# PATA_Breakout_2.net
KiCad netlist of a schematic drawn in EAGLE
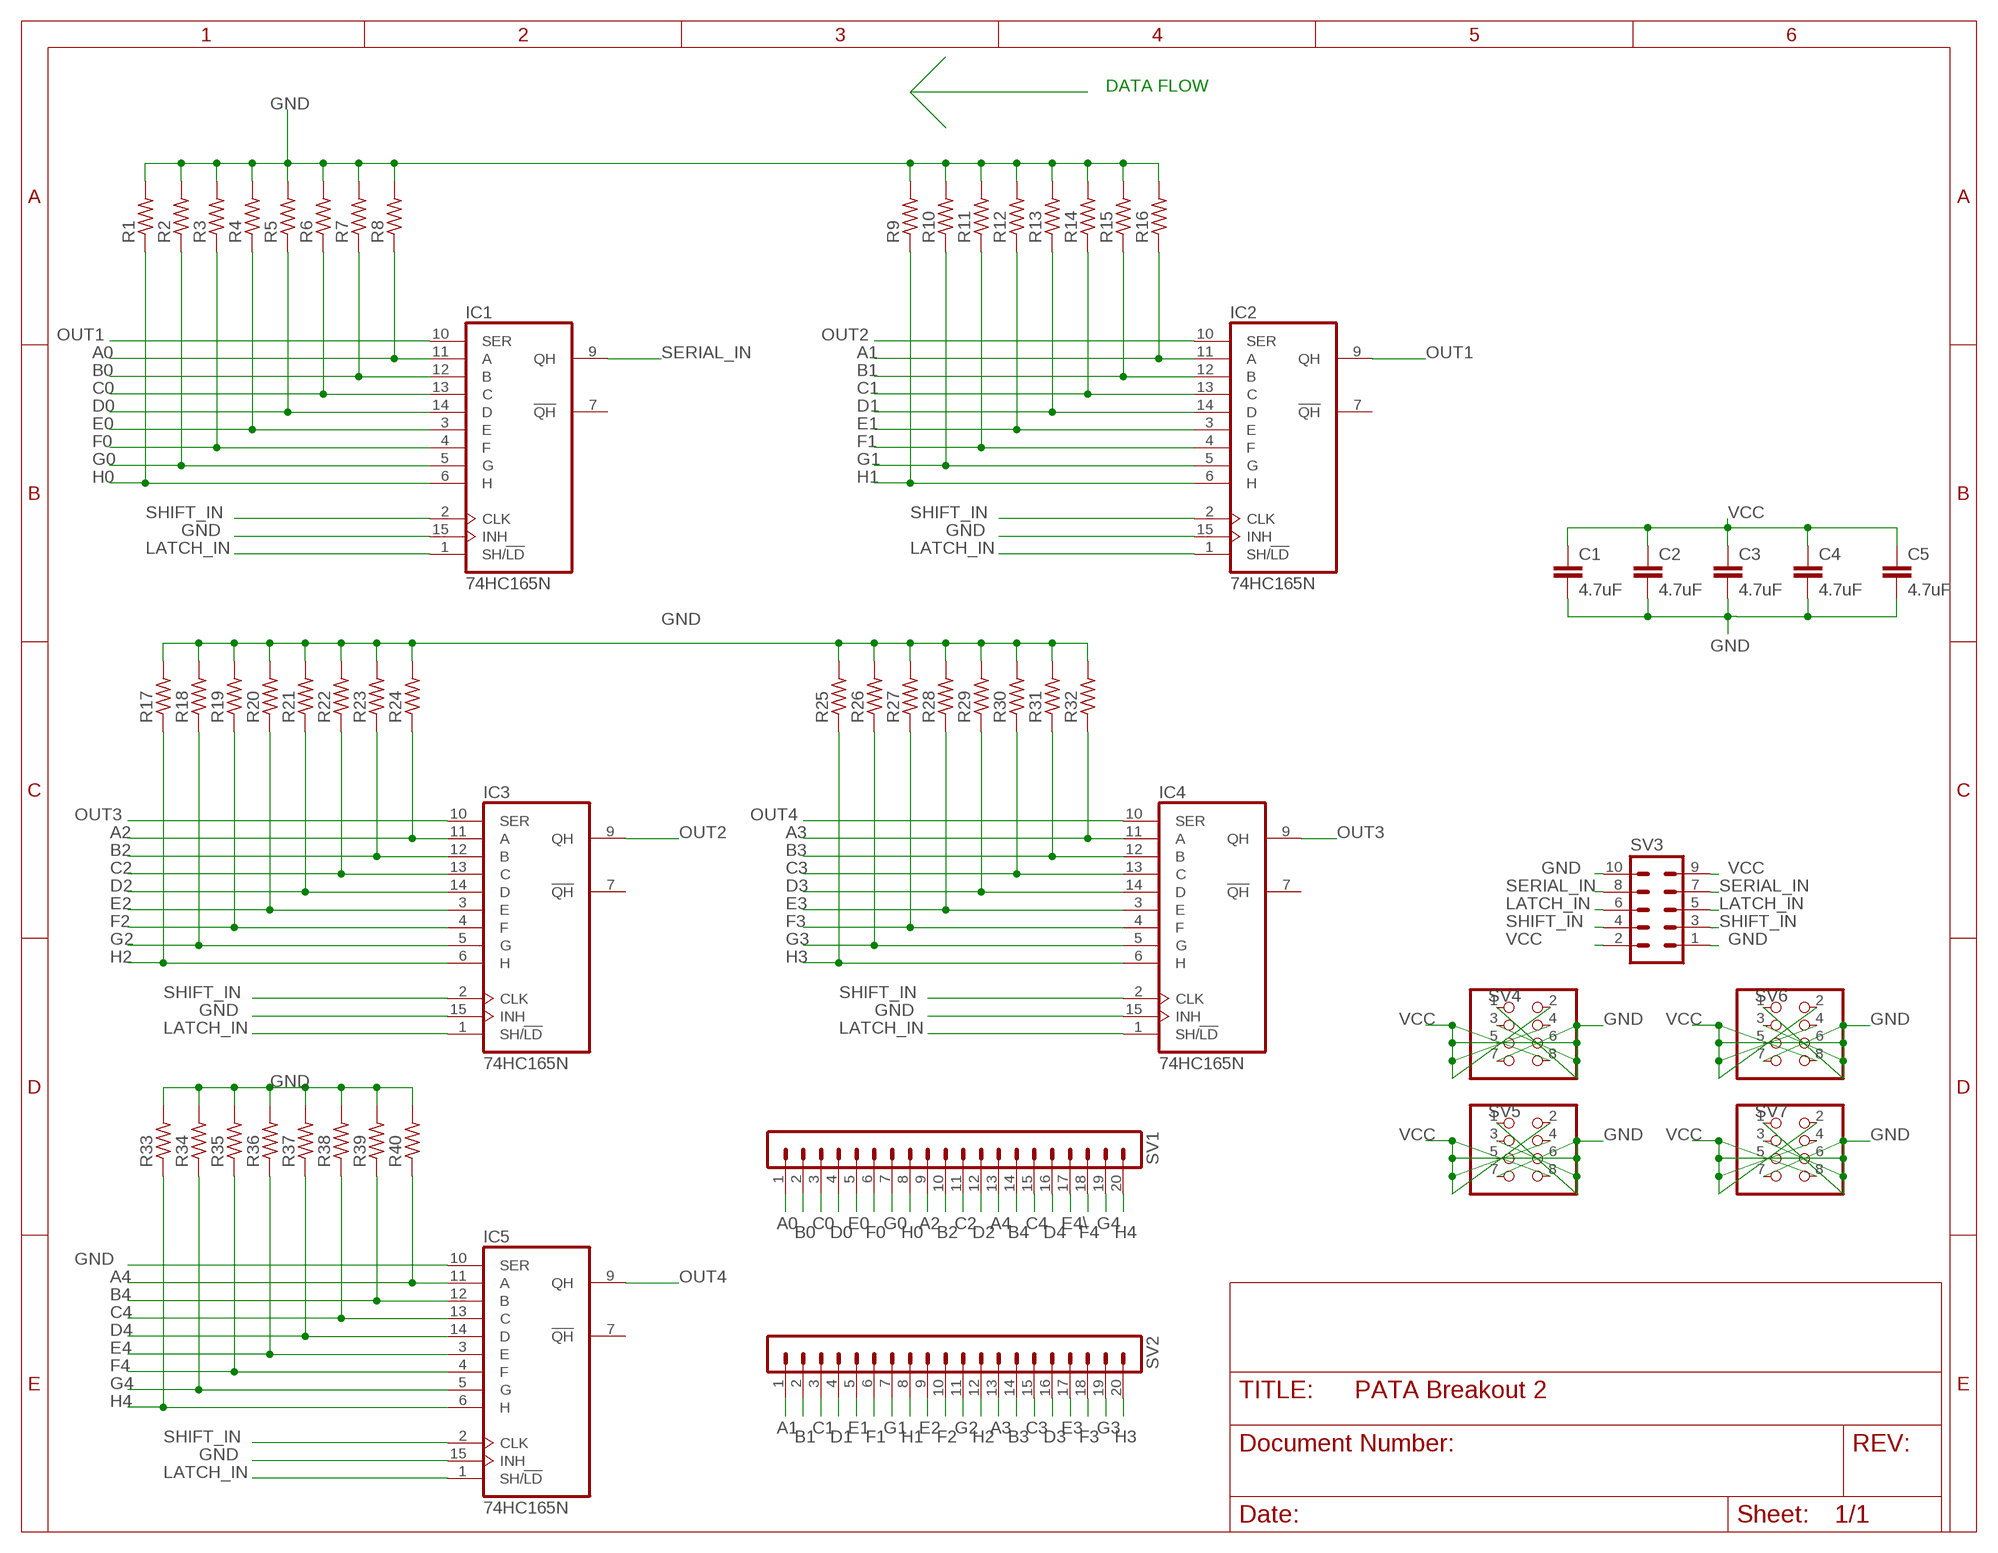
[diagram p0: schematic, sheet 1]

(export (version "E")
  (design (tool "Eeschema 10.0.6"))
  (components
    (comp (ref "C1")
      (value "4.7uF")
      (footprint "eagle-import:C050-024X044")
      (libsource (lib "eagle-import") (part "C-EU050-024X044"))
    )
    (comp (ref "C2")
      (value "4.7uF")
      (footprint "eagle-import:C050-024X044")
      (libsource (lib "eagle-import") (part "C-EU050-024X044"))
    )
    (comp (ref "C3")
      (value "4.7uF")
      (footprint "eagle-import:C050-024X044")
      (libsource (lib "eagle-import") (part "C-EU050-024X044"))
    )
    (comp (ref "C4")
      (value "4.7uF")
      (footprint "eagle-import:C050-024X044")
      (libsource (lib "eagle-import") (part "C-EU050-024X044"))
    )
    (comp (ref "C5")
      (value "4.7uF")
      (footprint "eagle-import:C050-024X044")
      (libsource (lib "eagle-import") (part "C-EU050-024X044"))
    )
    (comp (ref "IC1")
      (value "74HC165N")
      (footprint "eagle-import:DIL16")
      (libsource (lib "eagle-import") (part "74165NHC"))
    )
    (comp (ref "IC2")
      (value "74HC165N")
      (footprint "eagle-import:DIL16")
      (libsource (lib "eagle-import") (part "74165NHC"))
    )
    (comp (ref "IC3")
      (value "74HC165N")
      (footprint "eagle-import:DIL16")
      (libsource (lib "eagle-import") (part "74165NHC"))
    )
    (comp (ref "IC4")
      (value "74HC165N")
      (footprint "eagle-import:DIL16")
      (libsource (lib "eagle-import") (part "74165NHC"))
    )
    (comp (ref "IC5")
      (value "74HC165N")
      (footprint "eagle-import:DIL16")
      (libsource (lib "eagle-import") (part "74165NHC"))
    )
    (comp (ref "R1")
      (value "R-US_0204/5")
      (footprint "eagle-import:0204_5")
      (libsource (lib "eagle-import") (part "R-US_0204/5"))
    )
    (comp (ref "R2")
      (value "R-US_0204/5")
      (footprint "eagle-import:0204_5")
      (libsource (lib "eagle-import") (part "R-US_0204/5"))
    )
    (comp (ref "R3")
      (value "R-US_0204/5")
      (footprint "eagle-import:0204_5")
      (libsource (lib "eagle-import") (part "R-US_0204/5"))
    )
    (comp (ref "R4")
      (value "R-US_0204/5")
      (footprint "eagle-import:0204_5")
      (libsource (lib "eagle-import") (part "R-US_0204/5"))
    )
    (comp (ref "R5")
      (value "R-US_0204/5")
      (footprint "eagle-import:0204_5")
      (libsource (lib "eagle-import") (part "R-US_0204/5"))
    )
    (comp (ref "R6")
      (value "R-US_0204/5")
      (footprint "eagle-import:0204_5")
      (libsource (lib "eagle-import") (part "R-US_0204/5"))
    )
    (comp (ref "R7")
      (value "R-US_0204/5")
      (footprint "eagle-import:0204_5")
      (libsource (lib "eagle-import") (part "R-US_0204/5"))
    )
    (comp (ref "R8")
      (value "R-US_0204/5")
      (footprint "eagle-import:0204_5")
      (libsource (lib "eagle-import") (part "R-US_0204/5"))
    )
    (comp (ref "R9")
      (value "R-US_0204/5")
      (footprint "eagle-import:0204_5")
      (libsource (lib "eagle-import") (part "R-US_0204/5"))
    )
    (comp (ref "R10")
      (value "R-US_0204/5")
      (footprint "eagle-import:0204_5")
      (libsource (lib "eagle-import") (part "R-US_0204/5"))
    )
    (comp (ref "R11")
      (value "R-US_0204/5")
      (footprint "eagle-import:0204_5")
      (libsource (lib "eagle-import") (part "R-US_0204/5"))
    )
    (comp (ref "R12")
      (value "R-US_0204/5")
      (footprint "eagle-import:0204_5")
      (libsource (lib "eagle-import") (part "R-US_0204/5"))
    )
    (comp (ref "R13")
      (value "R-US_0204/5")
      (footprint "eagle-import:0204_5")
      (libsource (lib "eagle-import") (part "R-US_0204/5"))
    )
    (comp (ref "R14")
      (value "R-US_0204/5")
      (footprint "eagle-import:0204_5")
      (libsource (lib "eagle-import") (part "R-US_0204/5"))
    )
    (comp (ref "R15")
      (value "R-US_0204/5")
      (footprint "eagle-import:0204_5")
      (libsource (lib "eagle-import") (part "R-US_0204/5"))
    )
    (comp (ref "R16")
      (value "R-US_0204/5")
      (footprint "eagle-import:0204_5")
      (libsource (lib "eagle-import") (part "R-US_0204/5"))
    )
    (comp (ref "R17")
      (value "R-US_0204/5")
      (footprint "eagle-import:0204_5")
      (libsource (lib "eagle-import") (part "R-US_0204/5"))
    )
    (comp (ref "R18")
      (value "R-US_0204/5")
      (footprint "eagle-import:0204_5")
      (libsource (lib "eagle-import") (part "R-US_0204/5"))
    )
    (comp (ref "R19")
      (value "R-US_0204/5")
      (footprint "eagle-import:0204_5")
      (libsource (lib "eagle-import") (part "R-US_0204/5"))
    )
    (comp (ref "R20")
      (value "R-US_0204/5")
      (footprint "eagle-import:0204_5")
      (libsource (lib "eagle-import") (part "R-US_0204/5"))
    )
    (comp (ref "R21")
      (value "R-US_0204/5")
      (footprint "eagle-import:0204_5")
      (libsource (lib "eagle-import") (part "R-US_0204/5"))
    )
    (comp (ref "R22")
      (value "R-US_0204/5")
      (footprint "eagle-import:0204_5")
      (libsource (lib "eagle-import") (part "R-US_0204/5"))
    )
    (comp (ref "R23")
      (value "R-US_0204/5")
      (footprint "eagle-import:0204_5")
      (libsource (lib "eagle-import") (part "R-US_0204/5"))
    )
    (comp (ref "R24")
      (value "R-US_0204/5")
      (footprint "eagle-import:0204_5")
      (libsource (lib "eagle-import") (part "R-US_0204/5"))
    )
    (comp (ref "R25")
      (value "R-US_0204/5")
      (footprint "eagle-import:0204_5")
      (libsource (lib "eagle-import") (part "R-US_0204/5"))
    )
    (comp (ref "R26")
      (value "R-US_0204/5")
      (footprint "eagle-import:0204_5")
      (libsource (lib "eagle-import") (part "R-US_0204/5"))
    )
    (comp (ref "R27")
      (value "R-US_0204/5")
      (footprint "eagle-import:0204_5")
      (libsource (lib "eagle-import") (part "R-US_0204/5"))
    )
    (comp (ref "R28")
      (value "R-US_0204/5")
      (footprint "eagle-import:0204_5")
      (libsource (lib "eagle-import") (part "R-US_0204/5"))
    )
    (comp (ref "R29")
      (value "R-US_0204/5")
      (footprint "eagle-import:0204_5")
      (libsource (lib "eagle-import") (part "R-US_0204/5"))
    )
    (comp (ref "R30")
      (value "R-US_0204/5")
      (footprint "eagle-import:0204_5")
      (libsource (lib "eagle-import") (part "R-US_0204/5"))
    )
    (comp (ref "R31")
      (value "R-US_0204/5")
      (footprint "eagle-import:0204_5")
      (libsource (lib "eagle-import") (part "R-US_0204/5"))
    )
    (comp (ref "R32")
      (value "R-US_0204/5")
      (footprint "eagle-import:0204_5")
      (libsource (lib "eagle-import") (part "R-US_0204/5"))
    )
    (comp (ref "R33")
      (value "R-US_0204/5")
      (footprint "eagle-import:0204_5")
      (libsource (lib "eagle-import") (part "R-US_0204/5"))
    )
    (comp (ref "R34")
      (value "R-US_0204/5")
      (footprint "eagle-import:0204_5")
      (libsource (lib "eagle-import") (part "R-US_0204/5"))
    )
    (comp (ref "R35")
      (value "R-US_0204/5")
      (footprint "eagle-import:0204_5")
      (libsource (lib "eagle-import") (part "R-US_0204/5"))
    )
    (comp (ref "R36")
      (value "R-US_0204/5")
      (footprint "eagle-import:0204_5")
      (libsource (lib "eagle-import") (part "R-US_0204/5"))
    )
    (comp (ref "R37")
      (value "R-US_0204/5")
      (footprint "eagle-import:0204_5")
      (libsource (lib "eagle-import") (part "R-US_0204/5"))
    )
    (comp (ref "R38")
      (value "R-US_0204/5")
      (footprint "eagle-import:0204_5")
      (libsource (lib "eagle-import") (part "R-US_0204/5"))
    )
    (comp (ref "R39")
      (value "R-US_0204/5")
      (footprint "eagle-import:0204_5")
      (libsource (lib "eagle-import") (part "R-US_0204/5"))
    )
    (comp (ref "R40")
      (value "R-US_0204/5")
      (footprint "eagle-import:0204_5")
      (libsource (lib "eagle-import") (part "R-US_0204/5"))
    )
    (comp (ref "SV1")
      (value "MA20-1")
      (footprint "eagle-import:MA20-1")
      (libsource (lib "eagle-import") (part "MA20-1"))
    )
    (comp (ref "SV2")
      (value "MA20-1")
      (footprint "eagle-import:MA20-1")
      (libsource (lib "eagle-import") (part "MA20-1"))
    )
    (comp (ref "SV3")
      (value "MA05-2")
      (footprint "eagle-import:MA05-2")
      (libsource (lib "eagle-import") (part "MA05-2"))
    )
    (comp (ref "SV4")
      (value "PINHD-2X4")
      (footprint "eagle-import:2X04")
      (libsource (lib "eagle-import") (part "PINHD-2X4"))
    )
    (comp (ref "SV5")
      (value "PINHD-2X4")
      (footprint "eagle-import:2X04")
      (libsource (lib "eagle-import") (part "PINHD-2X4"))
    )
    (comp (ref "SV6")
      (value "PINHD-2X4")
      (footprint "eagle-import:2X04")
      (libsource (lib "eagle-import") (part "PINHD-2X4"))
    )
    (comp (ref "SV7")
      (value "PINHD-2X4")
      (footprint "eagle-import:2X04")
      (libsource (lib "eagle-import") (part "PINHD-2X4"))
    )
  )
  (nets
    (net (code "1") (name "/A0") (class "Default")
      (node (ref "IC1") (pin "11") (pinfunction "A_11") (pintype "input"))
      (node (ref "R8") (pin "1") (pinfunction "1_1") (pintype "passive"))
      (node (ref "SV1") (pin "1") (pinfunction "1_1") (pintype "passive"))
    )
    (net (code "2") (name "/A1") (class "Default")
      (node (ref "IC2") (pin "11") (pinfunction "A_11") (pintype "input"))
      (node (ref "R16") (pin "1") (pinfunction "1_1") (pintype "passive"))
      (node (ref "SV2") (pin "1") (pinfunction "1_1") (pintype "passive"))
    )
    (net (code "3") (name "/A2") (class "Default")
      (node (ref "IC3") (pin "11") (pinfunction "A_11") (pintype "input"))
      (node (ref "R24") (pin "1") (pinfunction "1_1") (pintype "passive"))
      (node (ref "SV1") (pin "9") (pinfunction "9_9") (pintype "passive"))
    )
    (net (code "4") (name "/A3") (class "Default")
      (node (ref "IC4") (pin "11") (pinfunction "A_11") (pintype "input"))
      (node (ref "R32") (pin "1") (pinfunction "1_1") (pintype "passive"))
      (node (ref "SV2") (pin "13") (pinfunction "13_13") (pintype "passive"))
    )
    (net (code "5") (name "/A4") (class "Default")
      (node (ref "IC5") (pin "11") (pinfunction "A_11") (pintype "input"))
      (node (ref "R40") (pin "1") (pinfunction "1_1") (pintype "passive"))
      (node (ref "SV1") (pin "13") (pinfunction "13_13") (pintype "passive"))
    )
    (net (code "6") (name "/B0") (class "Default")
      (node (ref "IC1") (pin "12") (pinfunction "B_12") (pintype "input"))
      (node (ref "R7") (pin "1") (pinfunction "1_1") (pintype "passive"))
      (node (ref "SV1") (pin "2") (pinfunction "2_2") (pintype "passive"))
    )
    (net (code "7") (name "/B1") (class "Default")
      (node (ref "IC2") (pin "12") (pinfunction "B_12") (pintype "input"))
      (node (ref "R15") (pin "1") (pinfunction "1_1") (pintype "passive"))
      (node (ref "SV2") (pin "2") (pinfunction "2_2") (pintype "passive"))
    )
    (net (code "8") (name "/B2") (class "Default")
      (node (ref "IC3") (pin "12") (pinfunction "B_12") (pintype "input"))
      (node (ref "R23") (pin "1") (pinfunction "1_1") (pintype "passive"))
      (node (ref "SV1") (pin "10") (pinfunction "10_10") (pintype "passive"))
    )
    (net (code "9") (name "/B3") (class "Default")
      (node (ref "IC4") (pin "12") (pinfunction "B_12") (pintype "input"))
      (node (ref "R31") (pin "1") (pinfunction "1_1") (pintype "passive"))
      (node (ref "SV2") (pin "14") (pinfunction "14_14") (pintype "passive"))
    )
    (net (code "10") (name "/B4") (class "Default")
      (node (ref "IC5") (pin "12") (pinfunction "B_12") (pintype "input"))
      (node (ref "R39") (pin "1") (pinfunction "1_1") (pintype "passive"))
      (node (ref "SV1") (pin "14") (pinfunction "14_14") (pintype "passive"))
    )
    (net (code "11") (name "/C0") (class "Default")
      (node (ref "IC1") (pin "13") (pinfunction "C_13") (pintype "input"))
      (node (ref "R6") (pin "1") (pinfunction "1_1") (pintype "passive"))
      (node (ref "SV1") (pin "3") (pinfunction "3_3") (pintype "passive"))
    )
    (net (code "12") (name "/C1") (class "Default")
      (node (ref "IC2") (pin "13") (pinfunction "C_13") (pintype "input"))
      (node (ref "R14") (pin "1") (pinfunction "1_1") (pintype "passive"))
      (node (ref "SV2") (pin "3") (pinfunction "3_3") (pintype "passive"))
    )
    (net (code "13") (name "/C2") (class "Default")
      (node (ref "IC3") (pin "13") (pinfunction "C_13") (pintype "input"))
      (node (ref "R22") (pin "1") (pinfunction "1_1") (pintype "passive"))
      (node (ref "SV1") (pin "11") (pinfunction "11_11") (pintype "passive"))
    )
    (net (code "14") (name "/C3") (class "Default")
      (node (ref "IC4") (pin "13") (pinfunction "C_13") (pintype "input"))
      (node (ref "R30") (pin "1") (pinfunction "1_1") (pintype "passive"))
      (node (ref "SV2") (pin "15") (pinfunction "15_15") (pintype "passive"))
    )
    (net (code "15") (name "/C4") (class "Default")
      (node (ref "IC5") (pin "13") (pinfunction "C_13") (pintype "input"))
      (node (ref "R38") (pin "1") (pinfunction "1_1") (pintype "passive"))
      (node (ref "SV1") (pin "15") (pinfunction "15_15") (pintype "passive"))
    )
    (net (code "16") (name "/D0") (class "Default")
      (node (ref "IC1") (pin "14") (pinfunction "D_14") (pintype "input"))
      (node (ref "R5") (pin "1") (pinfunction "1_1") (pintype "passive"))
      (node (ref "SV1") (pin "4") (pinfunction "4_4") (pintype "passive"))
    )
    (net (code "17") (name "/D1") (class "Default")
      (node (ref "IC2") (pin "14") (pinfunction "D_14") (pintype "input"))
      (node (ref "R13") (pin "1") (pinfunction "1_1") (pintype "passive"))
      (node (ref "SV2") (pin "4") (pinfunction "4_4") (pintype "passive"))
    )
    (net (code "18") (name "/D2") (class "Default")
      (node (ref "IC3") (pin "14") (pinfunction "D_14") (pintype "input"))
      (node (ref "R21") (pin "1") (pinfunction "1_1") (pintype "passive"))
      (node (ref "SV1") (pin "12") (pinfunction "12_12") (pintype "passive"))
    )
    (net (code "19") (name "/D3") (class "Default")
      (node (ref "IC4") (pin "14") (pinfunction "D_14") (pintype "input"))
      (node (ref "R29") (pin "1") (pinfunction "1_1") (pintype "passive"))
      (node (ref "SV2") (pin "16") (pinfunction "16_16") (pintype "passive"))
    )
    (net (code "20") (name "/D4") (class "Default")
      (node (ref "IC5") (pin "14") (pinfunction "D_14") (pintype "input"))
      (node (ref "R37") (pin "1") (pinfunction "1_1") (pintype "passive"))
      (node (ref "SV1") (pin "16") (pinfunction "16_16") (pintype "passive"))
    )
    (net (code "21") (name "/E0") (class "Default")
      (node (ref "IC1") (pin "3") (pinfunction "E_3") (pintype "input"))
      (node (ref "R4") (pin "1") (pinfunction "1_1") (pintype "passive"))
      (node (ref "SV1") (pin "5") (pinfunction "5_5") (pintype "passive"))
    )
    (net (code "22") (name "/E1") (class "Default")
      (node (ref "IC2") (pin "3") (pinfunction "E_3") (pintype "input"))
      (node (ref "R12") (pin "1") (pinfunction "1_1") (pintype "passive"))
      (node (ref "SV2") (pin "5") (pinfunction "5_5") (pintype "passive"))
    )
    (net (code "23") (name "/E2") (class "Default")
      (node (ref "IC3") (pin "3") (pinfunction "E_3") (pintype "input"))
      (node (ref "R20") (pin "1") (pinfunction "1_1") (pintype "passive"))
      (node (ref "SV2") (pin "9") (pinfunction "9_9") (pintype "passive"))
    )
    (net (code "24") (name "/E3") (class "Default")
      (node (ref "IC4") (pin "3") (pinfunction "E_3") (pintype "input"))
      (node (ref "R28") (pin "1") (pinfunction "1_1") (pintype "passive"))
      (node (ref "SV2") (pin "17") (pinfunction "17_17") (pintype "passive"))
    )
    (net (code "25") (name "/E4") (class "Default")
      (node (ref "IC5") (pin "3") (pinfunction "E_3") (pintype "input"))
      (node (ref "R36") (pin "1") (pinfunction "1_1") (pintype "passive"))
    )
    (net (code "26") (name "/E4\\") (class "Default")
      (node (ref "SV1") (pin "17") (pinfunction "17_17") (pintype "passive"))
    )
    (net (code "27") (name "/F0") (class "Default")
      (node (ref "IC1") (pin "4") (pinfunction "F_4") (pintype "input"))
      (node (ref "R3") (pin "1") (pinfunction "1_1") (pintype "passive"))
      (node (ref "SV1") (pin "6") (pinfunction "6_6") (pintype "passive"))
    )
    (net (code "28") (name "/F1") (class "Default")
      (node (ref "IC2") (pin "4") (pinfunction "F_4") (pintype "input"))
      (node (ref "R11") (pin "1") (pinfunction "1_1") (pintype "passive"))
      (node (ref "SV2") (pin "6") (pinfunction "6_6") (pintype "passive"))
    )
    (net (code "29") (name "/F2") (class "Default")
      (node (ref "IC3") (pin "4") (pinfunction "F_4") (pintype "input"))
      (node (ref "R19") (pin "1") (pinfunction "1_1") (pintype "passive"))
      (node (ref "SV2") (pin "10") (pinfunction "10_10") (pintype "passive"))
    )
    (net (code "30") (name "/F3") (class "Default")
      (node (ref "IC4") (pin "4") (pinfunction "F_4") (pintype "input"))
      (node (ref "R27") (pin "1") (pinfunction "1_1") (pintype "passive"))
      (node (ref "SV2") (pin "18") (pinfunction "18_18") (pintype "passive"))
    )
    (net (code "31") (name "/F4") (class "Default")
      (node (ref "IC5") (pin "4") (pinfunction "F_4") (pintype "input"))
      (node (ref "R35") (pin "1") (pinfunction "1_1") (pintype "passive"))
      (node (ref "SV1") (pin "18") (pinfunction "18_18") (pintype "passive"))
    )
    (net (code "32") (name "/G0") (class "Default")
      (node (ref "IC1") (pin "5") (pinfunction "G_5") (pintype "input"))
      (node (ref "R2") (pin "1") (pinfunction "1_1") (pintype "passive"))
      (node (ref "SV1") (pin "7") (pinfunction "7_7") (pintype "passive"))
    )
    (net (code "33") (name "/G1") (class "Default")
      (node (ref "IC2") (pin "5") (pinfunction "G_5") (pintype "input"))
      (node (ref "R10") (pin "1") (pinfunction "1_1") (pintype "passive"))
      (node (ref "SV2") (pin "7") (pinfunction "7_7") (pintype "passive"))
    )
    (net (code "34") (name "/G2") (class "Default")
      (node (ref "IC3") (pin "5") (pinfunction "G_5") (pintype "input"))
      (node (ref "R18") (pin "1") (pinfunction "1_1") (pintype "passive"))
      (node (ref "SV2") (pin "11") (pinfunction "11_11") (pintype "passive"))
    )
    (net (code "35") (name "/G3") (class "Default")
      (node (ref "IC4") (pin "5") (pinfunction "G_5") (pintype "input"))
      (node (ref "R26") (pin "1") (pinfunction "1_1") (pintype "passive"))
      (node (ref "SV2") (pin "19") (pinfunction "19_19") (pintype "passive"))
    )
    (net (code "36") (name "/G4") (class "Default")
      (node (ref "IC5") (pin "5") (pinfunction "G_5") (pintype "input"))
      (node (ref "R34") (pin "1") (pinfunction "1_1") (pintype "passive"))
      (node (ref "SV1") (pin "19") (pinfunction "19_19") (pintype "passive"))
    )
    (net (code "37") (name "/GND") (class "Default")
      (node (ref "C1") (pin "2") (pinfunction "2_2") (pintype "passive"))
      (node (ref "C2") (pin "2") (pinfunction "2_2") (pintype "passive"))
      (node (ref "C3") (pin "2") (pinfunction "2_2") (pintype "passive"))
      (node (ref "C4") (pin "2") (pinfunction "2_2") (pintype "passive"))
      (node (ref "C5") (pin "2") (pinfunction "2_2") (pintype "passive"))
      (node (ref "IC1") (pin "15") (pinfunction "INH_15") (pintype "input"))
      (node (ref "IC2") (pin "15") (pinfunction "INH_15") (pintype "input"))
      (node (ref "IC3") (pin "15") (pinfunction "INH_15") (pintype "input"))
      (node (ref "IC4") (pin "15") (pinfunction "INH_15") (pintype "input"))
      (node (ref "IC5") (pin "10") (pinfunction "SER_10") (pintype "input"))
      (node (ref "IC5") (pin "15") (pinfunction "INH_15") (pintype "input"))
      (node (ref "R1") (pin "2") (pinfunction "2_2") (pintype "passive"))
      (node (ref "R10") (pin "2") (pinfunction "2_2") (pintype "passive"))
      (node (ref "R11") (pin "2") (pinfunction "2_2") (pintype "passive"))
      (node (ref "R12") (pin "2") (pinfunction "2_2") (pintype "passive"))
      (node (ref "R13") (pin "2") (pinfunction "2_2") (pintype "passive"))
      (node (ref "R14") (pin "2") (pinfunction "2_2") (pintype "passive"))
      (node (ref "R15") (pin "2") (pinfunction "2_2") (pintype "passive"))
      (node (ref "R16") (pin "2") (pinfunction "2_2") (pintype "passive"))
      (node (ref "R17") (pin "2") (pinfunction "2_2") (pintype "passive"))
      (node (ref "R18") (pin "2") (pinfunction "2_2") (pintype "passive"))
      (node (ref "R19") (pin "2") (pinfunction "2_2") (pintype "passive"))
      (node (ref "R2") (pin "2") (pinfunction "2_2") (pintype "passive"))
      (node (ref "R20") (pin "2") (pinfunction "2_2") (pintype "passive"))
      (node (ref "R21") (pin "2") (pinfunction "2_2") (pintype "passive"))
      (node (ref "R22") (pin "2") (pinfunction "2_2") (pintype "passive"))
      (node (ref "R23") (pin "2") (pinfunction "2_2") (pintype "passive"))
      (node (ref "R24") (pin "2") (pinfunction "2_2") (pintype "passive"))
      (node (ref "R25") (pin "2") (pinfunction "2_2") (pintype "passive"))
      (node (ref "R26") (pin "2") (pinfunction "2_2") (pintype "passive"))
      (node (ref "R27") (pin "2") (pinfunction "2_2") (pintype "passive"))
      (node (ref "R28") (pin "2") (pinfunction "2_2") (pintype "passive"))
      (node (ref "R29") (pin "2") (pinfunction "2_2") (pintype "passive"))
      (node (ref "R3") (pin "2") (pinfunction "2_2") (pintype "passive"))
      (node (ref "R30") (pin "2") (pinfunction "2_2") (pintype "passive"))
      (node (ref "R31") (pin "2") (pinfunction "2_2") (pintype "passive"))
      (node (ref "R32") (pin "2") (pinfunction "2_2") (pintype "passive"))
      (node (ref "R33") (pin "2") (pinfunction "2_2") (pintype "passive"))
      (node (ref "R34") (pin "2") (pinfunction "2_2") (pintype "passive"))
      (node (ref "R35") (pin "2") (pinfunction "2_2") (pintype "passive"))
      (node (ref "R36") (pin "2") (pinfunction "2_2") (pintype "passive"))
      (node (ref "R37") (pin "2") (pinfunction "2_2") (pintype "passive"))
      (node (ref "R38") (pin "2") (pinfunction "2_2") (pintype "passive"))
      (node (ref "R39") (pin "2") (pinfunction "2_2") (pintype "passive"))
      (node (ref "R4") (pin "2") (pinfunction "2_2") (pintype "passive"))
      (node (ref "R40") (pin "2") (pinfunction "2_2") (pintype "passive"))
      (node (ref "R5") (pin "2") (pinfunction "2_2") (pintype "passive"))
      (node (ref "R6") (pin "2") (pinfunction "2_2") (pintype "passive"))
      (node (ref "R7") (pin "2") (pinfunction "2_2") (pintype "passive"))
      (node (ref "R8") (pin "2") (pinfunction "2_2") (pintype "passive"))
      (node (ref "R9") (pin "2") (pinfunction "2_2") (pintype "passive"))
      (node (ref "SV3") (pin "1") (pinfunction "1_1") (pintype "passive"))
      (node (ref "SV3") (pin "10") (pinfunction "10_10") (pintype "passive"))
      (node (ref "SV4") (pin "1") (pinfunction "1_1") (pintype "passive"))
      (node (ref "SV4") (pin "3") (pinfunction "3_3") (pintype "passive"))
      (node (ref "SV4") (pin "5") (pinfunction "5_5") (pintype "passive"))
      (node (ref "SV4") (pin "7") (pinfunction "7_7") (pintype "passive"))
      (node (ref "SV5") (pin "1") (pinfunction "1_1") (pintype "passive"))
      (node (ref "SV5") (pin "3") (pinfunction "3_3") (pintype "passive"))
      (node (ref "SV5") (pin "5") (pinfunction "5_5") (pintype "passive"))
      (node (ref "SV5") (pin "7") (pinfunction "7_7") (pintype "passive"))
      (node (ref "SV6") (pin "1") (pinfunction "1_1") (pintype "passive"))
      (node (ref "SV6") (pin "3") (pinfunction "3_3") (pintype "passive"))
      (node (ref "SV6") (pin "5") (pinfunction "5_5") (pintype "passive"))
      (node (ref "SV6") (pin "7") (pinfunction "7_7") (pintype "passive"))
      (node (ref "SV7") (pin "1") (pinfunction "1_1") (pintype "passive"))
      (node (ref "SV7") (pin "3") (pinfunction "3_3") (pintype "passive"))
      (node (ref "SV7") (pin "5") (pinfunction "5_5") (pintype "passive"))
      (node (ref "SV7") (pin "7") (pinfunction "7_7") (pintype "passive"))
    )
    (net (code "38") (name "/H0") (class "Default")
      (node (ref "IC1") (pin "6") (pinfunction "H_6") (pintype "input"))
      (node (ref "R1") (pin "1") (pinfunction "1_1") (pintype "passive"))
      (node (ref "SV1") (pin "8") (pinfunction "8_8") (pintype "passive"))
    )
    (net (code "39") (name "/H1") (class "Default")
      (node (ref "IC2") (pin "6") (pinfunction "H_6") (pintype "input"))
      (node (ref "R9") (pin "1") (pinfunction "1_1") (pintype "passive"))
      (node (ref "SV2") (pin "8") (pinfunction "8_8") (pintype "passive"))
    )
    (net (code "40") (name "/H2") (class "Default")
      (node (ref "IC3") (pin "6") (pinfunction "H_6") (pintype "input"))
      (node (ref "R17") (pin "1") (pinfunction "1_1") (pintype "passive"))
      (node (ref "SV2") (pin "12") (pinfunction "12_12") (pintype "passive"))
    )
    (net (code "41") (name "/H3") (class "Default")
      (node (ref "IC4") (pin "6") (pinfunction "H_6") (pintype "input"))
      (node (ref "R25") (pin "1") (pinfunction "1_1") (pintype "passive"))
      (node (ref "SV2") (pin "20") (pinfunction "20_20") (pintype "passive"))
    )
    (net (code "42") (name "/H4") (class "Default")
      (node (ref "IC5") (pin "6") (pinfunction "H_6") (pintype "input"))
      (node (ref "R33") (pin "1") (pinfunction "1_1") (pintype "passive"))
      (node (ref "SV1") (pin "20") (pinfunction "20_20") (pintype "passive"))
    )
    (net (code "43") (name "/LATCH_IN") (class "Default")
      (node (ref "IC1") (pin "1") (pinfunction "SH/~{LD}_1") (pintype "input"))
      (node (ref "IC2") (pin "1") (pinfunction "SH/~{LD}_1") (pintype "input"))
      (node (ref "IC3") (pin "1") (pinfunction "SH/~{LD}_1") (pintype "input"))
      (node (ref "IC4") (pin "1") (pinfunction "SH/~{LD}_1") (pintype "input"))
      (node (ref "IC5") (pin "1") (pinfunction "SH/~{LD}_1") (pintype "input"))
      (node (ref "SV3") (pin "5") (pinfunction "5_5") (pintype "passive"))
      (node (ref "SV3") (pin "6") (pinfunction "6_6") (pintype "passive"))
    )
    (net (code "44") (name "/OUT1") (class "Default")
      (node (ref "IC1") (pin "10") (pinfunction "SER_10") (pintype "input"))
      (node (ref "IC2") (pin "9") (pinfunction "QH_9") (pintype "output"))
    )
    (net (code "45") (name "/OUT2") (class "Default")
      (node (ref "IC2") (pin "10") (pinfunction "SER_10") (pintype "input"))
      (node (ref "IC3") (pin "9") (pinfunction "QH_9") (pintype "output"))
    )
    (net (code "46") (name "/OUT3") (class "Default")
      (node (ref "IC3") (pin "10") (pinfunction "SER_10") (pintype "input"))
      (node (ref "IC4") (pin "9") (pinfunction "QH_9") (pintype "output"))
    )
    (net (code "47") (name "/OUT4") (class "Default")
      (node (ref "IC4") (pin "10") (pinfunction "SER_10") (pintype "input"))
      (node (ref "IC5") (pin "9") (pinfunction "QH_9") (pintype "output"))
    )
    (net (code "48") (name "/SERIAL_IN") (class "Default")
      (node (ref "IC1") (pin "9") (pinfunction "QH_9") (pintype "output"))
      (node (ref "SV3") (pin "7") (pinfunction "7_7") (pintype "passive"))
      (node (ref "SV3") (pin "8") (pinfunction "8_8") (pintype "passive"))
    )
    (net (code "49") (name "/SHIFT_IN") (class "Default")
      (node (ref "IC1") (pin "2") (pinfunction "CLK_2") (pintype "input"))
      (node (ref "IC2") (pin "2") (pinfunction "CLK_2") (pintype "input"))
      (node (ref "IC3") (pin "2") (pinfunction "CLK_2") (pintype "input"))
      (node (ref "IC4") (pin "2") (pinfunction "CLK_2") (pintype "input"))
      (node (ref "IC5") (pin "2") (pinfunction "CLK_2") (pintype "input"))
      (node (ref "SV3") (pin "3") (pinfunction "3_3") (pintype "passive"))
      (node (ref "SV3") (pin "4") (pinfunction "4_4") (pintype "passive"))
    )
    (net (code "50") (name "/VCC") (class "Default")
      (node (ref "C1") (pin "1") (pinfunction "1_1") (pintype "passive"))
      (node (ref "C2") (pin "1") (pinfunction "1_1") (pintype "passive"))
      (node (ref "C3") (pin "1") (pinfunction "1_1") (pintype "passive"))
      (node (ref "C4") (pin "1") (pinfunction "1_1") (pintype "passive"))
      (node (ref "C5") (pin "1") (pinfunction "1_1") (pintype "passive"))
      (node (ref "SV3") (pin "2") (pinfunction "2_2") (pintype "passive"))
      (node (ref "SV3") (pin "9") (pinfunction "9_9") (pintype "passive"))
      (node (ref "SV4") (pin "2") (pinfunction "2_2") (pintype "passive"))
      (node (ref "SV4") (pin "4") (pinfunction "4_4") (pintype "passive"))
      (node (ref "SV4") (pin "6") (pinfunction "6_6") (pintype "passive"))
      (node (ref "SV4") (pin "8") (pinfunction "8_8") (pintype "passive"))
      (node (ref "SV5") (pin "2") (pinfunction "2_2") (pintype "passive"))
      (node (ref "SV5") (pin "4") (pinfunction "4_4") (pintype "passive"))
      (node (ref "SV5") (pin "6") (pinfunction "6_6") (pintype "passive"))
      (node (ref "SV5") (pin "8") (pinfunction "8_8") (pintype "passive"))
      (node (ref "SV6") (pin "2") (pinfunction "2_2") (pintype "passive"))
      (node (ref "SV6") (pin "4") (pinfunction "4_4") (pintype "passive"))
      (node (ref "SV6") (pin "6") (pinfunction "6_6") (pintype "passive"))
      (node (ref "SV6") (pin "8") (pinfunction "8_8") (pintype "passive"))
      (node (ref "SV7") (pin "2") (pinfunction "2_2") (pintype "passive"))
      (node (ref "SV7") (pin "4") (pinfunction "4_4") (pintype "passive"))
      (node (ref "SV7") (pin "6") (pinfunction "6_6") (pintype "passive"))
      (node (ref "SV7") (pin "8") (pinfunction "8_8") (pintype "passive"))
    )
    (net (code "51") (name "unconnected-(IC1A-~{QH}-Pad7)") (class "Default")
      (node (ref "IC1") (pin "7") (pinfunction "~{QH}_7") (pintype "output"))
    )
    (net (code "52") (name "unconnected-(IC2A-~{QH}-Pad7)") (class "Default")
      (node (ref "IC2") (pin "7") (pinfunction "~{QH}_7") (pintype "output"))
    )
    (net (code "53") (name "unconnected-(IC3A-~{QH}-Pad7)") (class "Default")
      (node (ref "IC3") (pin "7") (pinfunction "~{QH}_7") (pintype "output"))
    )
    (net (code "54") (name "unconnected-(IC4A-~{QH}-Pad7)") (class "Default")
      (node (ref "IC4") (pin "7") (pinfunction "~{QH}_7") (pintype "output"))
    )
    (net (code "55") (name "unconnected-(IC5A-~{QH}-Pad7)") (class "Default")
      (node (ref "IC5") (pin "7") (pinfunction "~{QH}_7") (pintype "output"))
    )
  )
)
